# Sheet5.net
KiCad netlist of a schematic drawn in Altium Designer
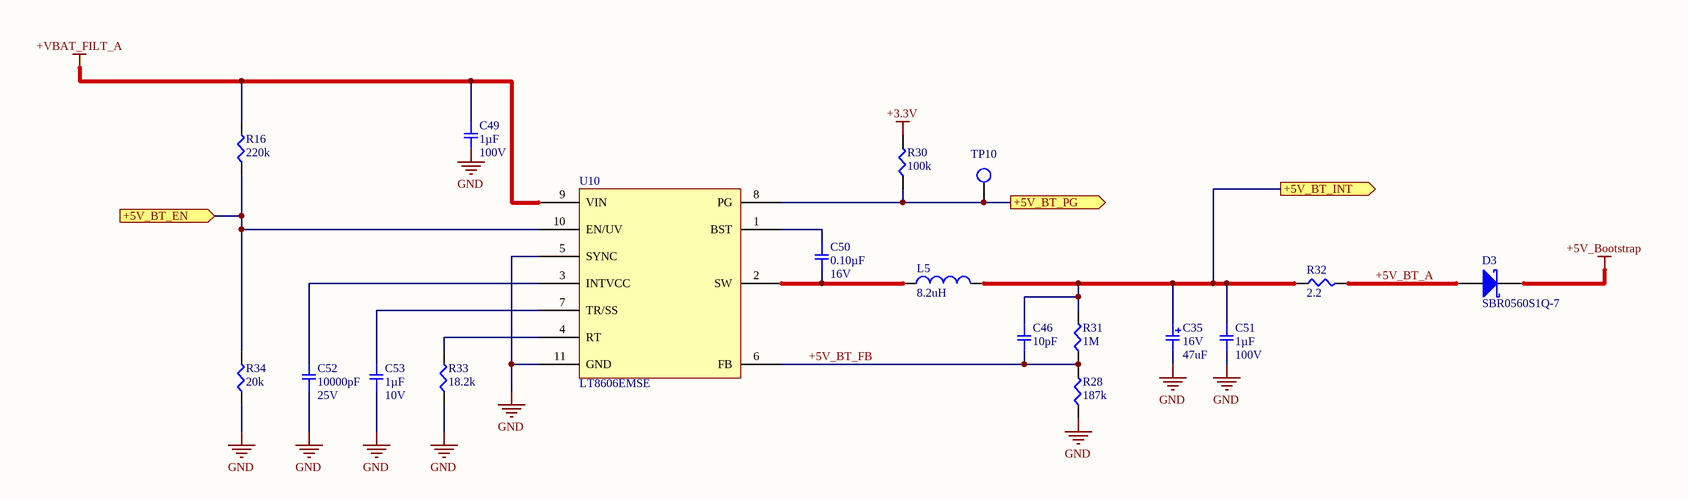
[diagram p0: Sheet5.SchDoc]

(export (version "E")
  (design (tool "Eeschema 10.0.6"))
  (components
    (comp (ref "C35")
      (value "47uF")
      (footprint "KEMET W - CAPMP7343X15N")
      (fields (field (name "VOLTAGE") "16V") (field (name "Comment") "T521W476M016ATE045"))
      (libsource (lib "KEMET") (part "T521W476M016ATE045"))
    )
    (comp (ref "C46")
      (value "10pF")
      (footprint "SMD-0402C")
      (description "CAP CER 10PF 50V NP0 0402")
      (fields
        (field (name "DIGI-KEY PART NUMBER") "490-10668-1-ND")
        (field (name "PART NUMBER") "GCM1555C1H100JA16D")
      )
      (libsource (lib "capacitor_murata_0402") (part "GCM1555C1H100JA16D"))
    )
    (comp (ref "C49")
      (value "1µF")
      (footprint "SMD-0805C")
      (description "CAP CER 1UF 100V X7S 0805")
      (fields
        (field (name "DIGI-KEY PART NUMBER") "490-10918-1-ND")
        (field (name "PART NUMBER") "GRJ21BC72A105KE11L")
        (field (name "VOLTAGE") "100V")
      )
      (libsource (lib "capacitor_murata_0805") (part "GRJ21BC72A105KE11L"))
    )
    (comp (ref "C50")
      (value "0.10µF")
      (footprint "SMD-0402C")
      (description "CAP CER 0.1UF 16V X7R 0402")
      (fields
        (field (name "DIGI-KEY PART NUMBER") "490-4759-1-ND")
        (field (name "PART NUMBER") "GCM155R71C104KA55D")
        (field (name "VOLTAGE") "16V")
      )
      (libsource (lib "capacitor_murata_0402") (part "GCM155R71C104KA55D"))
    )
    (comp (ref "C51")
      (value "1µF")
      (footprint "SMD-0805C")
      (description "CAP CER 1UF 100V X7S 0805")
      (fields
        (field (name "DIGI-KEY PART NUMBER") "490-10918-1-ND")
        (field (name "PART NUMBER") "GRJ21BC72A105KE11L")
        (field (name "VOLTAGE") "100V")
      )
      (libsource (lib "capacitor_murata_0805") (part "GRJ21BC72A105KE11L"))
    )
    (comp (ref "C52")
      (value "10000pF")
      (footprint "SMD-0402C")
      (description "CAP CER 10000PF 25V X7R 0402")
      (fields
        (field (name "DIGI-KEY PART NUMBER") "490-6043-1-ND")
        (field (name "PART NUMBER") "GCM155R71E103KA37D")
        (field (name "VOLTAGE") "25V")
      )
      (libsource (lib "capacitor_murata_0402") (part "GCM155R71E103KA37D"))
    )
    (comp (ref "C53")
      (value "1µF")
      (footprint "SMD-0402C")
      (description "CAP CER 1UF 10V X7S 0402")
      (fields
        (field (name "DIGI-KEY PART NUMBER") "490-13409-1-ND")
        (field (name "PART NUMBER") "GCM155C71A105KE38D")
        (field (name "VOLTAGE") "10V")
      )
      (libsource (lib "capacitor_murata_0402") (part "GCM155C71A105KE38D"))
    )
    (comp (ref "D3")
      (value "SBR0560S1Q-7")
      (footprint "SOD123")
      (libsource (lib "ModularPayload") (part "SBR0560S1Q-7"))
    )
    (comp (ref "L5")
      (value "8.2uH")
      (footprint "INDM4040X21N (XGL4020)")
      (fields (field (name "Comment") "XGL4020-822ME"))
      (libsource (lib "ModularPayload") (part "XGL4020-822ME"))
    )
    (comp (ref "R16")
      (value "220k")
      (footprint "SMD-0402-RES")
      (description "RES SMD 220K OHM 1% 1/10W 0402")
      (fields
        (field (name "PART NUMBER") "ERJ-2RKF2203X")
        (field (name "DIGI-KEY PART NUMBER") "P220KLCT-ND")
      )
      (libsource (lib "Panasonic_ERJ_0402") (part "ERJ-2RKF2203X"))
    )
    (comp (ref "R28")
      (value "187k")
      (footprint "SMD-0603-RES")
      (description "RES SMD 187K OHM 1% 1/10W 0603")
      (fields
        (field (name "PART NUMBER") "ERJ-3EKF1873V")
        (field (name "DIGI-KEY PART NUMBER") "P187KHCT-ND")
      )
      (libsource (lib "Panasonic_ERJ_0603") (part "ERJ-3EKF1873V"))
    )
    (comp (ref "R30")
      (value "100k")
      (footprint "SMD-0402-RES")
      (description "RES SMD 100K OHM 5% 1/10W 0402")
      (fields (field (name "PART NUMBER") "ERJ-2GEJ104X") (field (name "DIGI-KEY PART NUMBER") "P100KJCT-ND"))
      (libsource (lib "Panasonic_ERJ_0402") (part "ERJ-2GEJ104X"))
    )
    (comp (ref "R31")
      (value "1M")
      (footprint "SMD-0603-RES")
      (description "RES SMD 1M OHM 1% 1/10W 0603")
      (fields
        (field (name "PART NUMBER") "ERJ-3EKF1004V")
        (field (name "DIGI-KEY PART NUMBER") "P1.00MHCT-ND")
      )
      (libsource (lib "Panasonic_ERJ_0603") (part "ERJ-3EKF1004V"))
    )
    (comp (ref "R32")
      (value "2.2")
      (footprint "SMD-0805-RES")
      (description "RES SMD 2.2 OHM 5% 1/8W 0805")
      (fields (field (name "PART NUMBER") "ERJ-6GEYJ2R2V") (field (name "DIGI-KEY PART NUMBER") "P2.2ACT-ND"))
      (libsource (lib "Panasonic_ERJ_0805") (part "ERJ-6GEYJ2R2V"))
    )
    (comp (ref "R33")
      (value "18.2k")
      (footprint "SMD-0402-RES")
      (description "RES SMD 18.2K OHM 1% 1/10W 0402")
      (fields
        (field (name "PART NUMBER") "ERJ-2RKF1822X")
        (field (name "DIGI-KEY PART NUMBER") "P18.2KLCT-ND")
      )
      (libsource (lib "Panasonic_ERJ_0402") (part "ERJ-2RKF1822X"))
    )
    (comp (ref "R34")
      (value "20k")
      (footprint "SMD-0402-RES")
      (description "RES SMD 20K OHM 1% 1/10W 0402")
      (fields
        (field (name "PART NUMBER") "ERJ-2RKF2002X")
        (field (name "DIGI-KEY PART NUMBER") "P20.0KLCT-ND")
      )
      (libsource (lib "Panasonic_ERJ_0402") (part "ERJ-2RKF2002X"))
    )
    (comp (ref "TP10") (value "TP") (footprint "TP_SMD_40") (libsource (lib "TP") (part "TP")))
    (comp (ref "U10")
      (value "LT8606EMSE")
      (footprint "TSSOP50P490X110_HS-11N (LT8606MSE)")
      (libsource (lib "ModularPayload") (part "LT8606EMSE"))
    )
  )
  (nets
    (net (code "1") (name "+3.3V") (class "Default")
      (node (ref "R30") (pin "2") (pinfunction "2_2") (pintype "passive"))
    )
    (net (code "2") (name "+5V_Bootstrap") (class "Default")
      (node (ref "D3") (pin "K") (pinfunction "K_K") (pintype "passive"))
    )
    (net (code "3") (name "+VBAT_FILT_A") (class "Default")
      (node (ref "C49") (pin "1") (pinfunction "1_1") (pintype "passive"))
      (node (ref "R16") (pin "2") (pinfunction "2_2") (pintype "passive"))
      (node (ref "U10") (pin "9") (pinfunction "VIN_9") (pintype "passive"))
    )
    (net (code "4") (name "/+5V_BT_A") (class "Default")
      (node (ref "D3") (pin "A") (pinfunction "A_A") (pintype "passive"))
      (node (ref "R32") (pin "2") (pinfunction "2_2") (pintype "passive"))
    )
    (net (code "5") (name "/+5V_BT_EN") (class "Default")
      (node (ref "R16") (pin "1") (pinfunction "1_1") (pintype "passive"))
      (node (ref "R34") (pin "2") (pinfunction "2_2") (pintype "passive"))
      (node (ref "U10") (pin "10") (pinfunction "EN/UV_10") (pintype "passive"))
    )
    (net (code "6") (name "/+5V_BT_FB") (class "Default")
      (node (ref "C46") (pin "2") (pinfunction "2_2") (pintype "passive"))
      (node (ref "R28") (pin "2") (pinfunction "2_2") (pintype "passive"))
      (node (ref "R31") (pin "1") (pinfunction "1_1") (pintype "passive"))
      (node (ref "U10") (pin "6") (pinfunction "FB_6") (pintype "passive"))
    )
    (net (code "7") (name "/+5V_BT_INT") (class "Default")
      (node (ref "C35") (pin "1") (pinfunction "1_1") (pintype "passive"))
      (node (ref "C46") (pin "1") (pinfunction "1_1") (pintype "passive"))
      (node (ref "C51") (pin "1") (pinfunction "1_1") (pintype "passive"))
      (node (ref "L5") (pin "2") (pinfunction "2_2") (pintype "passive"))
      (node (ref "R31") (pin "2") (pinfunction "2_2") (pintype "passive"))
      (node (ref "R32") (pin "1") (pinfunction "1_1") (pintype "passive"))
    )
    (net (code "8") (name "/+5V_BT_PG") (class "Default")
      (node (ref "R30") (pin "1") (pinfunction "1_1") (pintype "passive"))
      (node (ref "TP10") (pin "1") (pintype "passive"))
      (node (ref "U10") (pin "8") (pinfunction "PG_8") (pintype "passive"))
    )
    (net (code "9") (name "GND") (class "Default")
      (node (ref "C35") (pin "2") (pinfunction "2_2") (pintype "passive"))
      (node (ref "C49") (pin "2") (pinfunction "2_2") (pintype "passive"))
      (node (ref "C51") (pin "2") (pinfunction "2_2") (pintype "passive"))
      (node (ref "C52") (pin "1") (pinfunction "1_1") (pintype "passive"))
      (node (ref "C53") (pin "1") (pinfunction "1_1") (pintype "passive"))
      (node (ref "R28") (pin "1") (pinfunction "1_1") (pintype "passive"))
      (node (ref "R33") (pin "1") (pinfunction "1_1") (pintype "passive"))
      (node (ref "R34") (pin "1") (pinfunction "1_1") (pintype "passive"))
      (node (ref "U10") (pin "11") (pinfunction "GND_11") (pintype "passive"))
      (node (ref "U10") (pin "5") (pinfunction "SYNC_5") (pintype "passive"))
    )
    (net (code "10") (name "Net-(U10-BST)") (class "Default")
      (node (ref "C50") (pin "1") (pinfunction "1_1") (pintype "passive"))
      (node (ref "U10") (pin "1") (pinfunction "BST_1") (pintype "passive"))
    )
    (net (code "11") (name "Net-(U10-INTVCC)") (class "Default")
      (node (ref "C52") (pin "2") (pinfunction "2_2") (pintype "passive"))
      (node (ref "U10") (pin "3") (pinfunction "INTVCC_3") (pintype "passive"))
    )
    (net (code "12") (name "Net-(U10-RT)") (class "Default")
      (node (ref "R33") (pin "2") (pinfunction "2_2") (pintype "passive"))
      (node (ref "U10") (pin "4") (pinfunction "RT_4") (pintype "passive"))
    )
    (net (code "13") (name "Net-(U10-SW)") (class "Default")
      (node (ref "C50") (pin "2") (pinfunction "2_2") (pintype "passive"))
      (node (ref "L5") (pin "1") (pinfunction "1_1") (pintype "passive"))
      (node (ref "U10") (pin "2") (pinfunction "SW_2") (pintype "passive"))
    )
    (net (code "14") (name "Net-(U10-TR{slash}SS)") (class "Default")
      (node (ref "C53") (pin "2") (pinfunction "2_2") (pintype "passive"))
      (node (ref "U10") (pin "7") (pinfunction "TR/SS_7") (pintype "passive"))
    )
  )
)
